# PassiveFilter.net
KiCad netlist of a schematic drawn in Altium Designer
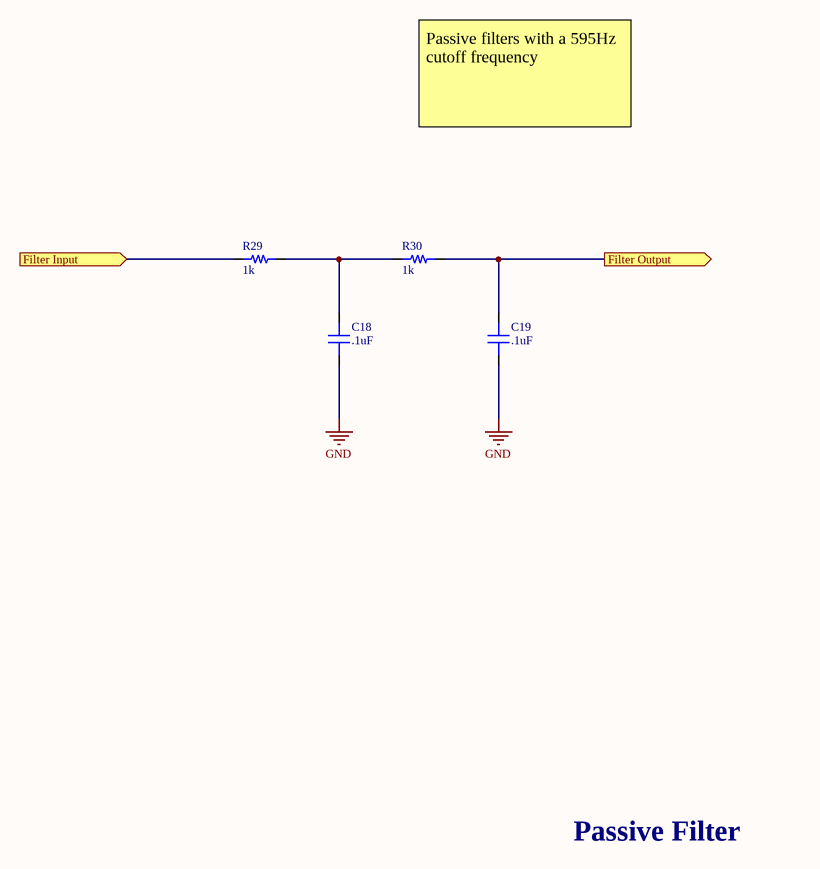
[diagram p0: PassiveFilter.SchDoc]

(export (version "E")
  (design (tool "Eeschema 10.0.6"))
  (components
    (comp (ref "C18")
      (value "capacitor")
      (footprint "0603")
      (description "Generic 0603 capacitor")
      (fields (field (name "CAPACITANCE") ".1uF") (field (name "VOLTAGE") "50"))
      (libsource (lib "altlib") (part "capacitor"))
    )
    (comp (ref "C19")
      (value "capacitor")
      (footprint "0603")
      (description "Generic 0603 capacitor")
      (fields (field (name "CAPACITANCE") ".1uF") (field (name "VOLTAGE") "50"))
      (libsource (lib "altlib") (part "capacitor"))
    )
    (comp (ref "R29")
      (value "1k")
      (footprint "RES 0603/1608")
      (fields (field (name "RESISTANCE") "1k"))
      (libsource (lib "altlib") (part "Resistor"))
    )
    (comp (ref "R30")
      (value "1k")
      (footprint "RES 0603/1608")
      (fields (field (name "RESISTANCE") "1k"))
      (libsource (lib "altlib") (part "Resistor"))
    )
  )
  (nets
    (net (code "1") (name "/Filter Input") (class "Default")
      (node (ref "R29") (pin "1") (pinfunction "1_1") (pintype "passive"))
    )
    (net (code "2") (name "/Filter Output") (class "Default")
      (node (ref "C19") (pin "2") (pinfunction "2_2") (pintype "passive"))
      (node (ref "R30") (pin "2") (pinfunction "2_2") (pintype "passive"))
    )
    (net (code "3") (name "GND") (class "Default")
      (node (ref "C18") (pin "1") (pinfunction "1_1") (pintype "passive"))
      (node (ref "C19") (pin "1") (pinfunction "1_1") (pintype "passive"))
    )
    (net (code "4") (name "Net-(C18-Pad2)") (class "Default")
      (node (ref "C18") (pin "2") (pinfunction "2_2") (pintype "passive"))
      (node (ref "R29") (pin "2") (pinfunction "2_2") (pintype "passive"))
      (node (ref "R30") (pin "1") (pinfunction "1_1") (pintype "passive"))
    )
  )
)
